# horizontal_counter.net
KiCad netlist of a schematic drawn in Altium Designer
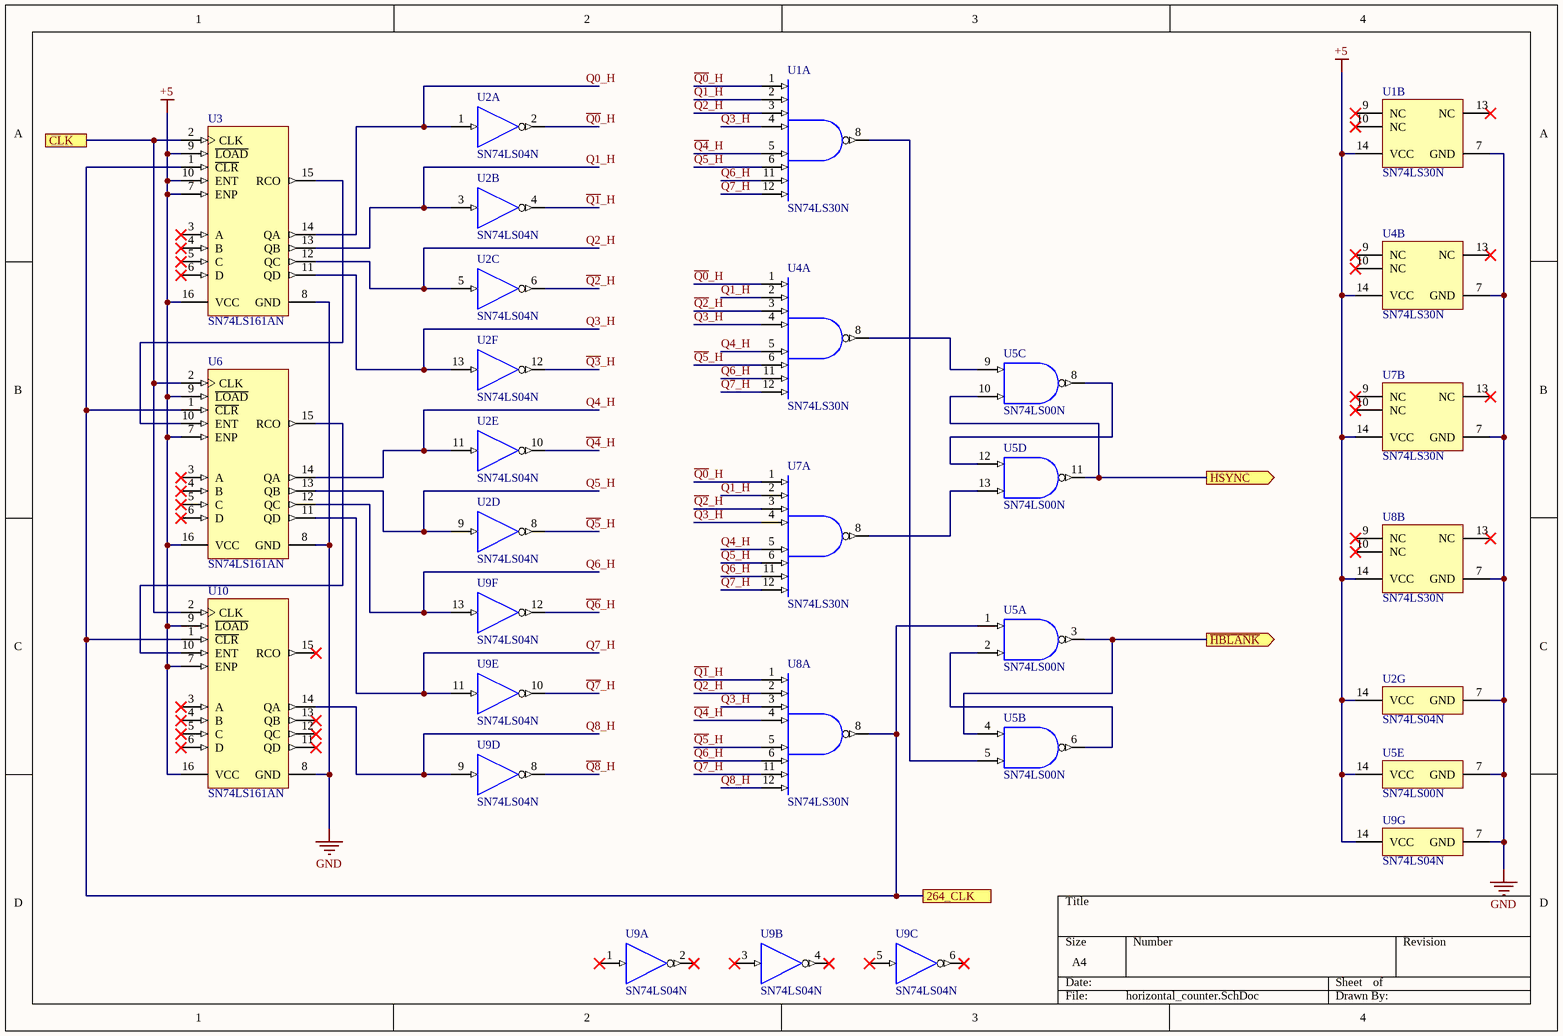
[diagram p0: horizontal_counter.SchDoc]

(export (version "E")
  (design (tool "Eeschema 10.0.6"))
  (components
    (comp (ref "U1")
      (value "SN74LS30N")
      (footprint "N0014A")
      (description "8-input positive-NAND gates, N0014A, TUBE")
      (fields
        (field (name "GENERIC PART NUMBER") "SN74LS30")
        (field (name "MANUFACTURER") "Texas Instruments")
      )
      (libsource (lib "Altium Content Vault") (part "TI-SN74XX30-D0014A-14"))
    )
    (comp (ref "U2")
      (value "SN74LS04N")
      (footprint "N0014A")
      (description "Hex inverters, N0014A, TUBE")
      (fields
        (field (name "MANUFACTURER") "Texas Instruments")
        (field (name "GENERIC PART NUMBER") "SN74LS04")
      )
      (libsource (lib "Altium Content Vault") (part "TI-CD_SNX4XXXXXX4X_19A-14"))
    )
    (comp (ref "U3")
      (value "SN74LS161AN")
      (footprint "N0016A")
      (description "Synchronous 4-Bit Binary Counters, N0016A, TUBE")
      (fields
        (field (name "GENERIC PART NUMBER") "SN74LS161A")
        (field (name "MANUFACTURER") "Texas Instruments")
      )
      (libsource (lib "Altium Content Vault") (part "TI-CD_SNX4XXX161_163X-16"))
    )
    (comp (ref "U4")
      (value "SN74LS30N")
      (footprint "N0014A")
      (description "8-input positive-NAND gates, N0014A, TUBE")
      (fields
        (field (name "GENERIC PART NUMBER") "SN74LS30")
        (field (name "MANUFACTURER") "Texas Instruments")
      )
      (libsource (lib "Altium Content Vault") (part "TI-SN74XX30-D0014A-14"))
    )
    (comp (ref "U5")
      (value "SN74LS00N")
      (footprint "N0014A")
      (description "Quad 2-input positive-NAND gates, N0014A, TUBE")
      (fields
        (field (name "MANUFACTURER") "Texas Instruments")
        (field (name "GENERIC PART NUMBER") "SN74LS00")
      )
      (libsource (lib "Altium Content Vault") (part "TI-NAND-4-2IN-14_G"))
    )
    (comp (ref "U6")
      (value "SN74LS161AN")
      (footprint "N0016A")
      (description "Synchronous 4-Bit Binary Counters, N0016A, TUBE")
      (fields
        (field (name "GENERIC PART NUMBER") "SN74LS161A")
        (field (name "MANUFACTURER") "Texas Instruments")
      )
      (libsource (lib "Altium Content Vault") (part "TI-CD_SNX4XXX161_163X-16"))
    )
    (comp (ref "U7")
      (value "SN74LS30N")
      (footprint "N0014A")
      (description "8-input positive-NAND gates, N0014A, TUBE")
      (fields
        (field (name "GENERIC PART NUMBER") "SN74LS30")
        (field (name "MANUFACTURER") "Texas Instruments")
      )
      (libsource (lib "Altium Content Vault") (part "TI-SN74XX30-D0014A-14"))
    )
    (comp (ref "U8")
      (value "SN74LS30N")
      (footprint "N0014A")
      (description "8-input positive-NAND gates, N0014A, TUBE")
      (fields
        (field (name "GENERIC PART NUMBER") "SN74LS30")
        (field (name "MANUFACTURER") "Texas Instruments")
      )
      (libsource (lib "Altium Content Vault") (part "TI-SN74XX30-D0014A-14"))
    )
    (comp (ref "U9")
      (value "SN74LS04N")
      (footprint "N0014A")
      (description "Hex inverters, N0014A, TUBE")
      (fields
        (field (name "MANUFACTURER") "Texas Instruments")
        (field (name "GENERIC PART NUMBER") "SN74LS04")
      )
      (libsource (lib "Altium Content Vault") (part "TI-CD_SNX4XXXXXX4X_19A-14"))
    )
    (comp (ref "U10")
      (value "SN74LS161AN")
      (footprint "N0016A")
      (description "Synchronous 4-Bit Binary Counters, N0016A, TUBE")
      (fields
        (field (name "GENERIC PART NUMBER") "SN74LS161A")
        (field (name "MANUFACTURER") "Texas Instruments")
      )
      (libsource (lib "Altium Content Vault") (part "TI-CD_SNX4XXX161_163X-16"))
    )
  )
  (nets
    (net (code "1") (name "+5") (class "Default")
      (node (ref "U1") (pin "14") (pinfunction "VCC_14") (pintype "power_in"))
      (node (ref "U10") (pin "16") (pinfunction "VCC_16") (pintype "power_in"))
      (node (ref "U10") (pin "7") (pinfunction "ENP_7") (pintype "input"))
      (node (ref "U10") (pin "9") (pinfunction "~{LOAD}_9") (pintype "input"))
      (node (ref "U2") (pin "14") (pinfunction "VCC_14") (pintype "power_in"))
      (node (ref "U3") (pin "10") (pinfunction "ENT_10") (pintype "input"))
      (node (ref "U3") (pin "16") (pinfunction "VCC_16") (pintype "power_in"))
      (node (ref "U3") (pin "7") (pinfunction "ENP_7") (pintype "input"))
      (node (ref "U3") (pin "9") (pinfunction "~{LOAD}_9") (pintype "input"))
      (node (ref "U4") (pin "14") (pinfunction "VCC_14") (pintype "power_in"))
      (node (ref "U5") (pin "14") (pinfunction "VCC_14") (pintype "power_in"))
      (node (ref "U6") (pin "16") (pinfunction "VCC_16") (pintype "power_in"))
      (node (ref "U6") (pin "7") (pinfunction "ENP_7") (pintype "input"))
      (node (ref "U6") (pin "9") (pinfunction "~{LOAD}_9") (pintype "input"))
      (node (ref "U7") (pin "14") (pinfunction "VCC_14") (pintype "power_in"))
      (node (ref "U8") (pin "14") (pinfunction "VCC_14") (pintype "power_in"))
      (node (ref "U9") (pin "14") (pinfunction "VCC_14") (pintype "power_in"))
    )
    (net (code "2") (name "/264_CLK") (class "Default")
      (node (ref "U10") (pin "1") (pinfunction "~{CLR}_1") (pintype "input"))
      (node (ref "U3") (pin "1") (pinfunction "~{CLR}_1") (pintype "input"))
      (node (ref "U5") (pin "1") (pinfunction "1A_1") (pintype "input"))
      (node (ref "U6") (pin "1") (pinfunction "~{CLR}_1") (pintype "input"))
      (node (ref "U8") (pin "8") (pinfunction "~{Y}_8") (pintype "output"))
    )
    (net (code "3") (name "/CLK") (class "Default")
      (node (ref "U10") (pin "2") (pinfunction "CLK_2") (pintype "input"))
      (node (ref "U3") (pin "2") (pinfunction "CLK_2") (pintype "input"))
      (node (ref "U6") (pin "2") (pinfunction "CLK_2") (pintype "input"))
    )
    (net (code "4") (name "/HSYNC") (class "Default")
      (node (ref "U5") (pin "10") (pinfunction "3B_10") (pintype "input"))
      (node (ref "U5") (pin "11") (pinfunction "4Y_11") (pintype "output"))
    )
    (net (code "5") (name "/Q0_H") (class "Default")
      (node (ref "U2") (pin "1") (pinfunction "1A_1") (pintype "input"))
      (node (ref "U3") (pin "14") (pinfunction "QA_14") (pintype "output"))
    )
    (net (code "6") (name "/Q1_H") (class "Default")
      (node (ref "U2") (pin "3") (pinfunction "2A_3") (pintype "input"))
      (node (ref "U3") (pin "13") (pinfunction "QB_13") (pintype "output"))
      (node (ref "U4") (pin "2") (pinfunction "B_2") (pintype "input"))
      (node (ref "U7") (pin "2") (pinfunction "B_2") (pintype "input"))
    )
    (net (code "7") (name "/Q2_H") (class "Default")
      (node (ref "U2") (pin "5") (pinfunction "3A_5") (pintype "input"))
      (node (ref "U3") (pin "12") (pinfunction "QC_12") (pintype "output"))
    )
    (net (code "8") (name "/Q3_H") (class "Default")
      (node (ref "U1") (pin "4") (pinfunction "D_4") (pintype "input"))
      (node (ref "U2") (pin "13") (pinfunction "6A_13") (pintype "input"))
      (node (ref "U3") (pin "11") (pinfunction "QD_11") (pintype "output"))
      (node (ref "U8") (pin "3") (pinfunction "C_3") (pintype "input"))
    )
    (net (code "9") (name "/Q4_H") (class "Default")
      (node (ref "U2") (pin "11") (pinfunction "5A_11") (pintype "input"))
      (node (ref "U4") (pin "5") (pinfunction "E_5") (pintype "input"))
      (node (ref "U6") (pin "14") (pinfunction "QA_14") (pintype "output"))
      (node (ref "U7") (pin "5") (pinfunction "E_5") (pintype "input"))
    )
    (net (code "10") (name "/Q5_H") (class "Default")
      (node (ref "U2") (pin "9") (pinfunction "4A_9") (pintype "input"))
      (node (ref "U6") (pin "13") (pinfunction "QB_13") (pintype "output"))
      (node (ref "U7") (pin "6") (pinfunction "F_6") (pintype "input"))
    )
    (net (code "11") (name "/Q6_H") (class "Default")
      (node (ref "U1") (pin "11") (pinfunction "G_11") (pintype "input"))
      (node (ref "U4") (pin "11") (pinfunction "G_11") (pintype "input"))
      (node (ref "U6") (pin "12") (pinfunction "QC_12") (pintype "output"))
      (node (ref "U7") (pin "11") (pinfunction "G_11") (pintype "input"))
      (node (ref "U9") (pin "13") (pinfunction "6A_13") (pintype "input"))
    )
    (net (code "12") (name "/Q7_H") (class "Default")
      (node (ref "U1") (pin "12") (pinfunction "H_12") (pintype "input"))
      (node (ref "U4") (pin "12") (pinfunction "H_12") (pintype "input"))
      (node (ref "U6") (pin "11") (pinfunction "QD_11") (pintype "output"))
      (node (ref "U7") (pin "12") (pinfunction "H_12") (pintype "input"))
      (node (ref "U9") (pin "11") (pinfunction "5A_11") (pintype "input"))
    )
    (net (code "13") (name "/Q8_H") (class "Default")
      (node (ref "U10") (pin "14") (pinfunction "QA_14") (pintype "output"))
      (node (ref "U8") (pin "12") (pinfunction "H_12") (pintype "input"))
      (node (ref "U9") (pin "9") (pinfunction "4A_9") (pintype "input"))
    )
    (net (code "14") (name "/~{HBLANK}") (class "Default")
      (node (ref "U5") (pin "3") (pinfunction "1Y_3") (pintype "output"))
      (node (ref "U5") (pin "4") (pinfunction "2A_4") (pintype "input"))
    )
    (net (code "15") (name "/~{Q0}_H") (class "Default")
      (node (ref "U1") (pin "1") (pinfunction "A_1") (pintype "input"))
      (node (ref "U2") (pin "2") (pinfunction "~{1Y}_2") (pintype "output"))
      (node (ref "U4") (pin "1") (pinfunction "A_1") (pintype "input"))
      (node (ref "U7") (pin "1") (pinfunction "A_1") (pintype "input"))
    )
    (net (code "16") (name "/~{Q1}_H") (class "Default")
      (node (ref "U1") (pin "2") (pinfunction "B_2") (pintype "input"))
      (node (ref "U2") (pin "4") (pinfunction "~{2Y}_4") (pintype "output"))
      (node (ref "U8") (pin "1") (pinfunction "A_1") (pintype "input"))
    )
    (net (code "17") (name "/~{Q2}_H") (class "Default")
      (node (ref "U1") (pin "3") (pinfunction "C_3") (pintype "input"))
      (node (ref "U2") (pin "6") (pinfunction "~{3Y}_6") (pintype "output"))
      (node (ref "U4") (pin "3") (pinfunction "C_3") (pintype "input"))
      (node (ref "U7") (pin "3") (pinfunction "C_3") (pintype "input"))
      (node (ref "U8") (pin "2") (pinfunction "B_2") (pintype "input"))
    )
    (net (code "18") (name "/~{Q3}_H") (class "Default")
      (node (ref "U2") (pin "12") (pinfunction "~{6Y}_12") (pintype "output"))
      (node (ref "U4") (pin "4") (pinfunction "D_4") (pintype "input"))
      (node (ref "U7") (pin "4") (pinfunction "D_4") (pintype "input"))
    )
    (net (code "19") (name "/~{Q4}_H") (class "Default")
      (node (ref "U1") (pin "5") (pinfunction "E_5") (pintype "input"))
      (node (ref "U2") (pin "10") (pinfunction "~{5Y}_10") (pintype "output"))
      (node (ref "U8") (pin "4") (pinfunction "D_4") (pintype "input"))
    )
    (net (code "20") (name "/~{Q5}_H") (class "Default")
      (node (ref "U1") (pin "6") (pinfunction "F_6") (pintype "input"))
      (node (ref "U2") (pin "8") (pinfunction "~{4Y}_8") (pintype "output"))
      (node (ref "U4") (pin "6") (pinfunction "F_6") (pintype "input"))
      (node (ref "U8") (pin "5") (pinfunction "E_5") (pintype "input"))
    )
    (net (code "21") (name "/~{Q6}_H") (class "Default")
      (node (ref "U8") (pin "6") (pinfunction "F_6") (pintype "input"))
      (node (ref "U9") (pin "12") (pinfunction "~{6Y}_12") (pintype "output"))
    )
    (net (code "22") (name "/~{Q7}_H") (class "Default")
      (node (ref "U8") (pin "11") (pinfunction "G_11") (pintype "input"))
      (node (ref "U9") (pin "10") (pinfunction "~{5Y}_10") (pintype "output"))
    )
    (net (code "23") (name "/~{Q8}_H") (class "Default")
      (node (ref "U9") (pin "8") (pinfunction "~{4Y}_8") (pintype "output"))
    )
    (net (code "24") (name "GND") (class "Default")
      (node (ref "U1") (pin "7") (pinfunction "GND_7") (pintype "power_in"))
      (node (ref "U10") (pin "8") (pinfunction "GND_8") (pintype "power_in"))
      (node (ref "U2") (pin "7") (pinfunction "GND_7") (pintype "power_in"))
      (node (ref "U3") (pin "8") (pinfunction "GND_8") (pintype "power_in"))
      (node (ref "U4") (pin "7") (pinfunction "GND_7") (pintype "power_in"))
      (node (ref "U5") (pin "7") (pinfunction "GND_7") (pintype "power_in"))
      (node (ref "U6") (pin "8") (pinfunction "GND_8") (pintype "power_in"))
      (node (ref "U7") (pin "7") (pinfunction "GND_7") (pintype "power_in"))
      (node (ref "U8") (pin "7") (pinfunction "GND_7") (pintype "power_in"))
      (node (ref "U9") (pin "7") (pinfunction "GND_7") (pintype "power_in"))
    )
    (net (code "25") (name "Net-(U1A-~{Y})") (class "Default")
      (node (ref "U1") (pin "8") (pinfunction "~{Y}_8") (pintype "output"))
      (node (ref "U5") (pin "5") (pinfunction "2B_5") (pintype "input"))
    )
    (net (code "26") (name "Net-(U3-RCO)") (class "Default")
      (node (ref "U3") (pin "15") (pinfunction "RCO_15") (pintype "output"))
      (node (ref "U6") (pin "10") (pinfunction "ENT_10") (pintype "input"))
    )
    (net (code "27") (name "Net-(U4A-~{Y})") (class "Default")
      (node (ref "U4") (pin "8") (pinfunction "~{Y}_8") (pintype "output"))
      (node (ref "U5") (pin "9") (pinfunction "3A_9") (pintype "input"))
    )
    (net (code "28") (name "Net-(U5A-1B)") (class "Default")
      (node (ref "U5") (pin "2") (pinfunction "1B_2") (pintype "input"))
      (node (ref "U5") (pin "6") (pinfunction "2Y_6") (pintype "output"))
    )
    (net (code "29") (name "Net-(U5C-3Y)") (class "Default")
      (node (ref "U5") (pin "12") (pinfunction "4A_12") (pintype "input"))
      (node (ref "U5") (pin "8") (pinfunction "3Y_8") (pintype "output"))
    )
    (net (code "30") (name "Net-(U5D-4B)") (class "Default")
      (node (ref "U5") (pin "13") (pinfunction "4B_13") (pintype "input"))
      (node (ref "U7") (pin "8") (pinfunction "~{Y}_8") (pintype "output"))
    )
    (net (code "31") (name "Net-(U10-ENT)") (class "Default")
      (node (ref "U10") (pin "10") (pinfunction "ENT_10") (pintype "input"))
      (node (ref "U6") (pin "15") (pinfunction "RCO_15") (pintype "output"))
    )
    (net (code "32") (name "unconnected-(U1B-NC-Pad9)") (class "Default")
      (node (ref "U1") (pin "9") (pinfunction "NC_9") (pintype "passive+no_connect"))
    )
    (net (code "33") (name "unconnected-(U1B-NC-Pad10)") (class "Default")
      (node (ref "U1") (pin "10") (pinfunction "NC_10") (pintype "passive+no_connect"))
    )
    (net (code "34") (name "unconnected-(U1B-NC-Pad13)") (class "Default")
      (node (ref "U1") (pin "13") (pinfunction "NC_13") (pintype "passive+no_connect"))
    )
    (net (code "35") (name "unconnected-(U3-A-Pad3)") (class "Default")
      (node (ref "U3") (pin "3") (pinfunction "A_3") (pintype "input+no_connect"))
    )
    (net (code "36") (name "unconnected-(U3-B-Pad4)") (class "Default")
      (node (ref "U3") (pin "4") (pinfunction "B_4") (pintype "input+no_connect"))
    )
    (net (code "37") (name "unconnected-(U3-C-Pad5)") (class "Default")
      (node (ref "U3") (pin "5") (pinfunction "C_5") (pintype "input+no_connect"))
    )
    (net (code "38") (name "unconnected-(U3-D-Pad6)") (class "Default")
      (node (ref "U3") (pin "6") (pinfunction "D_6") (pintype "input+no_connect"))
    )
    (net (code "39") (name "unconnected-(U4B-NC-Pad9)") (class "Default")
      (node (ref "U4") (pin "9") (pinfunction "NC_9") (pintype "passive+no_connect"))
    )
    (net (code "40") (name "unconnected-(U4B-NC-Pad10)") (class "Default")
      (node (ref "U4") (pin "10") (pinfunction "NC_10") (pintype "passive+no_connect"))
    )
    (net (code "41") (name "unconnected-(U4B-NC-Pad13)") (class "Default")
      (node (ref "U4") (pin "13") (pinfunction "NC_13") (pintype "passive+no_connect"))
    )
    (net (code "42") (name "unconnected-(U6-A-Pad3)") (class "Default")
      (node (ref "U6") (pin "3") (pinfunction "A_3") (pintype "input+no_connect"))
    )
    (net (code "43") (name "unconnected-(U6-B-Pad4)") (class "Default")
      (node (ref "U6") (pin "4") (pinfunction "B_4") (pintype "input+no_connect"))
    )
    (net (code "44") (name "unconnected-(U6-C-Pad5)") (class "Default")
      (node (ref "U6") (pin "5") (pinfunction "C_5") (pintype "input+no_connect"))
    )
    (net (code "45") (name "unconnected-(U6-D-Pad6)") (class "Default")
      (node (ref "U6") (pin "6") (pinfunction "D_6") (pintype "input+no_connect"))
    )
    (net (code "46") (name "unconnected-(U7B-NC-Pad9)") (class "Default")
      (node (ref "U7") (pin "9") (pinfunction "NC_9") (pintype "passive+no_connect"))
    )
    (net (code "47") (name "unconnected-(U7B-NC-Pad10)") (class "Default")
      (node (ref "U7") (pin "10") (pinfunction "NC_10") (pintype "passive+no_connect"))
    )
    (net (code "48") (name "unconnected-(U7B-NC-Pad13)") (class "Default")
      (node (ref "U7") (pin "13") (pinfunction "NC_13") (pintype "passive+no_connect"))
    )
    (net (code "49") (name "unconnected-(U8B-NC-Pad9)") (class "Default")
      (node (ref "U8") (pin "9") (pinfunction "NC_9") (pintype "passive+no_connect"))
    )
    (net (code "50") (name "unconnected-(U8B-NC-Pad10)") (class "Default")
      (node (ref "U8") (pin "10") (pinfunction "NC_10") (pintype "passive+no_connect"))
    )
    (net (code "51") (name "unconnected-(U8B-NC-Pad13)") (class "Default")
      (node (ref "U8") (pin "13") (pinfunction "NC_13") (pintype "passive+no_connect"))
    )
    (net (code "52") (name "unconnected-(U9A-1A-Pad1)") (class "Default")
      (node (ref "U9") (pin "1") (pinfunction "1A_1") (pintype "input+no_connect"))
    )
    (net (code "53") (name "unconnected-(U9A-~{1Y}-Pad2)") (class "Default")
      (node (ref "U9") (pin "2") (pinfunction "~{1Y}_2") (pintype "output+no_connect"))
    )
    (net (code "54") (name "unconnected-(U9B-2A-Pad3)") (class "Default")
      (node (ref "U9") (pin "3") (pinfunction "2A_3") (pintype "input+no_connect"))
    )
    (net (code "55") (name "unconnected-(U9B-~{2Y}-Pad4)") (class "Default")
      (node (ref "U9") (pin "4") (pinfunction "~{2Y}_4") (pintype "output+no_connect"))
    )
    (net (code "56") (name "unconnected-(U9C-3A-Pad5)") (class "Default")
      (node (ref "U9") (pin "5") (pinfunction "3A_5") (pintype "input+no_connect"))
    )
    (net (code "57") (name "unconnected-(U9C-~{3Y}-Pad6)") (class "Default")
      (node (ref "U9") (pin "6") (pinfunction "~{3Y}_6") (pintype "output+no_connect"))
    )
    (net (code "58") (name "unconnected-(U10-A-Pad3)") (class "Default")
      (node (ref "U10") (pin "3") (pinfunction "A_3") (pintype "input+no_connect"))
    )
    (net (code "59") (name "unconnected-(U10-B-Pad4)") (class "Default")
      (node (ref "U10") (pin "4") (pinfunction "B_4") (pintype "input+no_connect"))
    )
    (net (code "60") (name "unconnected-(U10-C-Pad5)") (class "Default")
      (node (ref "U10") (pin "5") (pinfunction "C_5") (pintype "input+no_connect"))
    )
    (net (code "61") (name "unconnected-(U10-D-Pad6)") (class "Default")
      (node (ref "U10") (pin "6") (pinfunction "D_6") (pintype "input+no_connect"))
    )
    (net (code "62") (name "unconnected-(U10-QB-Pad13)") (class "Default")
      (node (ref "U10") (pin "13") (pinfunction "QB_13") (pintype "output+no_connect"))
    )
    (net (code "63") (name "unconnected-(U10-QC-Pad12)") (class "Default")
      (node (ref "U10") (pin "12") (pinfunction "QC_12") (pintype "output+no_connect"))
    )
    (net (code "64") (name "unconnected-(U10-QD-Pad11)") (class "Default")
      (node (ref "U10") (pin "11") (pinfunction "QD_11") (pintype "output+no_connect"))
    )
    (net (code "65") (name "unconnected-(U10-RCO-Pad15)") (class "Default")
      (node (ref "U10") (pin "15") (pinfunction "RCO_15") (pintype "output+no_connect"))
    )
  )
)
